# Diode.net
KiCad netlist of a schematic drawn in Altium Designer
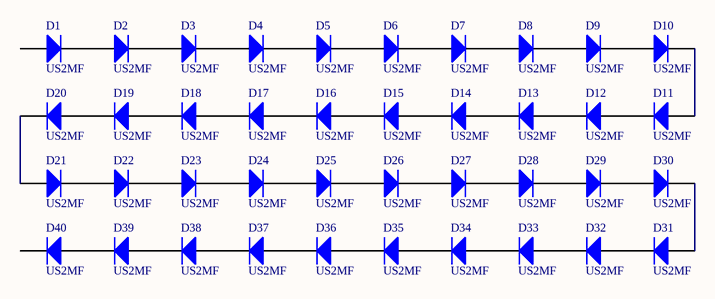
[diagram p0: Diode.SchDoc]

(export (version "E")
  (design (tool "Eeschema 10.0.6"))
  (components
    (comp (ref "D1")
      (value "US2MF")
      (footprint "DO-214AC")
      (description "DIODE - HyperFast 1kV")
      (fields (field (name "LCSC PART #") "C108845"))
      (libsource (lib "JLC_PCB") (part "US2MF"))
    )
    (comp (ref "D2")
      (value "US2MF")
      (footprint "DO-214AC")
      (description "DIODE - HyperFast 1kV")
      (fields (field (name "LCSC PART #") "C108845"))
      (libsource (lib "JLC_PCB") (part "US2MF"))
    )
    (comp (ref "D3")
      (value "US2MF")
      (footprint "DO-214AC")
      (description "DIODE - HyperFast 1kV")
      (fields (field (name "LCSC PART #") "C108845"))
      (libsource (lib "JLC_PCB") (part "US2MF"))
    )
    (comp (ref "D4")
      (value "US2MF")
      (footprint "DO-214AC")
      (description "DIODE - HyperFast 1kV")
      (fields (field (name "LCSC PART #") "C108845"))
      (libsource (lib "JLC_PCB") (part "US2MF"))
    )
    (comp (ref "D5")
      (value "US2MF")
      (footprint "DO-214AC")
      (description "DIODE - HyperFast 1kV")
      (fields (field (name "LCSC PART #") "C108845"))
      (libsource (lib "JLC_PCB") (part "US2MF"))
    )
    (comp (ref "D6")
      (value "US2MF")
      (footprint "DO-214AC")
      (description "DIODE - HyperFast 1kV")
      (fields (field (name "LCSC PART #") "C108845"))
      (libsource (lib "JLC_PCB") (part "US2MF"))
    )
    (comp (ref "D7")
      (value "US2MF")
      (footprint "DO-214AC")
      (description "DIODE - HyperFast 1kV")
      (fields (field (name "LCSC PART #") "C108845"))
      (libsource (lib "JLC_PCB") (part "US2MF"))
    )
    (comp (ref "D8")
      (value "US2MF")
      (footprint "DO-214AC")
      (description "DIODE - HyperFast 1kV")
      (fields (field (name "LCSC PART #") "C108845"))
      (libsource (lib "JLC_PCB") (part "US2MF"))
    )
    (comp (ref "D9")
      (value "US2MF")
      (footprint "DO-214AC")
      (description "DIODE - HyperFast 1kV")
      (fields (field (name "LCSC PART #") "C108845"))
      (libsource (lib "JLC_PCB") (part "US2MF"))
    )
    (comp (ref "D10")
      (value "US2MF")
      (footprint "DO-214AC")
      (description "DIODE - HyperFast 1kV")
      (fields (field (name "LCSC PART #") "C108845"))
      (libsource (lib "JLC_PCB") (part "US2MF"))
    )
    (comp (ref "D11")
      (value "US2MF")
      (footprint "DO-214AC")
      (description "DIODE - HyperFast 1kV")
      (fields (field (name "LCSC PART #") "C108845"))
      (libsource (lib "JLC_PCB") (part "US2MF"))
    )
    (comp (ref "D12")
      (value "US2MF")
      (footprint "DO-214AC")
      (description "DIODE - HyperFast 1kV")
      (fields (field (name "LCSC PART #") "C108845"))
      (libsource (lib "JLC_PCB") (part "US2MF"))
    )
    (comp (ref "D13")
      (value "US2MF")
      (footprint "DO-214AC")
      (description "DIODE - HyperFast 1kV")
      (fields (field (name "LCSC PART #") "C108845"))
      (libsource (lib "JLC_PCB") (part "US2MF"))
    )
    (comp (ref "D14")
      (value "US2MF")
      (footprint "DO-214AC")
      (description "DIODE - HyperFast 1kV")
      (fields (field (name "LCSC PART #") "C108845"))
      (libsource (lib "JLC_PCB") (part "US2MF"))
    )
    (comp (ref "D15")
      (value "US2MF")
      (footprint "DO-214AC")
      (description "DIODE - HyperFast 1kV")
      (fields (field (name "LCSC PART #") "C108845"))
      (libsource (lib "JLC_PCB") (part "US2MF"))
    )
    (comp (ref "D16")
      (value "US2MF")
      (footprint "DO-214AC")
      (description "DIODE - HyperFast 1kV")
      (fields (field (name "LCSC PART #") "C108845"))
      (libsource (lib "JLC_PCB") (part "US2MF"))
    )
    (comp (ref "D17")
      (value "US2MF")
      (footprint "DO-214AC")
      (description "DIODE - HyperFast 1kV")
      (fields (field (name "LCSC PART #") "C108845"))
      (libsource (lib "JLC_PCB") (part "US2MF"))
    )
    (comp (ref "D18")
      (value "US2MF")
      (footprint "DO-214AC")
      (description "DIODE - HyperFast 1kV")
      (fields (field (name "LCSC PART #") "C108845"))
      (libsource (lib "JLC_PCB") (part "US2MF"))
    )
    (comp (ref "D19")
      (value "US2MF")
      (footprint "DO-214AC")
      (description "DIODE - HyperFast 1kV")
      (fields (field (name "LCSC PART #") "C108845"))
      (libsource (lib "JLC_PCB") (part "US2MF"))
    )
    (comp (ref "D20")
      (value "US2MF")
      (footprint "DO-214AC")
      (description "DIODE - HyperFast 1kV")
      (fields (field (name "LCSC PART #") "C108845"))
      (libsource (lib "JLC_PCB") (part "US2MF"))
    )
    (comp (ref "D21")
      (value "US2MF")
      (footprint "DO-214AC")
      (description "DIODE - HyperFast 1kV")
      (fields (field (name "LCSC PART #") "C108845"))
      (libsource (lib "JLC_PCB") (part "US2MF"))
    )
    (comp (ref "D22")
      (value "US2MF")
      (footprint "DO-214AC")
      (description "DIODE - HyperFast 1kV")
      (fields (field (name "LCSC PART #") "C108845"))
      (libsource (lib "JLC_PCB") (part "US2MF"))
    )
    (comp (ref "D23")
      (value "US2MF")
      (footprint "DO-214AC")
      (description "DIODE - HyperFast 1kV")
      (fields (field (name "LCSC PART #") "C108845"))
      (libsource (lib "JLC_PCB") (part "US2MF"))
    )
    (comp (ref "D24")
      (value "US2MF")
      (footprint "DO-214AC")
      (description "DIODE - HyperFast 1kV")
      (fields (field (name "LCSC PART #") "C108845"))
      (libsource (lib "JLC_PCB") (part "US2MF"))
    )
    (comp (ref "D25")
      (value "US2MF")
      (footprint "DO-214AC")
      (description "DIODE - HyperFast 1kV")
      (fields (field (name "LCSC PART #") "C108845"))
      (libsource (lib "JLC_PCB") (part "US2MF"))
    )
    (comp (ref "D26")
      (value "US2MF")
      (footprint "DO-214AC")
      (description "DIODE - HyperFast 1kV")
      (fields (field (name "LCSC PART #") "C108845"))
      (libsource (lib "JLC_PCB") (part "US2MF"))
    )
    (comp (ref "D27")
      (value "US2MF")
      (footprint "DO-214AC")
      (description "DIODE - HyperFast 1kV")
      (fields (field (name "LCSC PART #") "C108845"))
      (libsource (lib "JLC_PCB") (part "US2MF"))
    )
    (comp (ref "D28")
      (value "US2MF")
      (footprint "DO-214AC")
      (description "DIODE - HyperFast 1kV")
      (fields (field (name "LCSC PART #") "C108845"))
      (libsource (lib "JLC_PCB") (part "US2MF"))
    )
    (comp (ref "D29")
      (value "US2MF")
      (footprint "DO-214AC")
      (description "DIODE - HyperFast 1kV")
      (fields (field (name "LCSC PART #") "C108845"))
      (libsource (lib "JLC_PCB") (part "US2MF"))
    )
    (comp (ref "D30")
      (value "US2MF")
      (footprint "DO-214AC")
      (description "DIODE - HyperFast 1kV")
      (fields (field (name "LCSC PART #") "C108845"))
      (libsource (lib "JLC_PCB") (part "US2MF"))
    )
    (comp (ref "D31")
      (value "US2MF")
      (footprint "DO-214AC")
      (description "DIODE - HyperFast 1kV")
      (fields (field (name "LCSC PART #") "C108845"))
      (libsource (lib "JLC_PCB") (part "US2MF"))
    )
    (comp (ref "D32")
      (value "US2MF")
      (footprint "DO-214AC")
      (description "DIODE - HyperFast 1kV")
      (fields (field (name "LCSC PART #") "C108845"))
      (libsource (lib "JLC_PCB") (part "US2MF"))
    )
    (comp (ref "D33")
      (value "US2MF")
      (footprint "DO-214AC")
      (description "DIODE - HyperFast 1kV")
      (fields (field (name "LCSC PART #") "C108845"))
      (libsource (lib "JLC_PCB") (part "US2MF"))
    )
    (comp (ref "D34")
      (value "US2MF")
      (footprint "DO-214AC")
      (description "DIODE - HyperFast 1kV")
      (fields (field (name "LCSC PART #") "C108845"))
      (libsource (lib "JLC_PCB") (part "US2MF"))
    )
    (comp (ref "D35")
      (value "US2MF")
      (footprint "DO-214AC")
      (description "DIODE - HyperFast 1kV")
      (fields (field (name "LCSC PART #") "C108845"))
      (libsource (lib "JLC_PCB") (part "US2MF"))
    )
    (comp (ref "D36")
      (value "US2MF")
      (footprint "DO-214AC")
      (description "DIODE - HyperFast 1kV")
      (fields (field (name "LCSC PART #") "C108845"))
      (libsource (lib "JLC_PCB") (part "US2MF"))
    )
    (comp (ref "D37")
      (value "US2MF")
      (footprint "DO-214AC")
      (description "DIODE - HyperFast 1kV")
      (fields (field (name "LCSC PART #") "C108845"))
      (libsource (lib "JLC_PCB") (part "US2MF"))
    )
    (comp (ref "D38")
      (value "US2MF")
      (footprint "DO-214AC")
      (description "DIODE - HyperFast 1kV")
      (fields (field (name "LCSC PART #") "C108845"))
      (libsource (lib "JLC_PCB") (part "US2MF"))
    )
    (comp (ref "D39")
      (value "US2MF")
      (footprint "DO-214AC")
      (description "DIODE - HyperFast 1kV")
      (fields (field (name "LCSC PART #") "C108845"))
      (libsource (lib "JLC_PCB") (part "US2MF"))
    )
    (comp (ref "D40")
      (value "US2MF")
      (footprint "DO-214AC")
      (description "DIODE - HyperFast 1kV")
      (fields (field (name "LCSC PART #") "C108845"))
      (libsource (lib "JLC_PCB") (part "US2MF"))
    )
  )
  (nets
    (net (code "1") (name "Net-(D1-K)") (class "Default")
      (node (ref "D1") (pin "1") (pinfunction "K_1") (pintype "passive"))
      (node (ref "D2") (pin "2") (pinfunction "A_2") (pintype "passive"))
    )
    (net (code "2") (name "Net-(D2-K)") (class "Default")
      (node (ref "D2") (pin "1") (pinfunction "K_1") (pintype "passive"))
      (node (ref "D3") (pin "2") (pinfunction "A_2") (pintype "passive"))
    )
    (net (code "3") (name "Net-(D3-K)") (class "Default")
      (node (ref "D3") (pin "1") (pinfunction "K_1") (pintype "passive"))
      (node (ref "D4") (pin "2") (pinfunction "A_2") (pintype "passive"))
    )
    (net (code "4") (name "Net-(D4-K)") (class "Default")
      (node (ref "D4") (pin "1") (pinfunction "K_1") (pintype "passive"))
      (node (ref "D5") (pin "2") (pinfunction "A_2") (pintype "passive"))
    )
    (net (code "5") (name "Net-(D5-K)") (class "Default")
      (node (ref "D5") (pin "1") (pinfunction "K_1") (pintype "passive"))
      (node (ref "D6") (pin "2") (pinfunction "A_2") (pintype "passive"))
    )
    (net (code "6") (name "Net-(D6-K)") (class "Default")
      (node (ref "D6") (pin "1") (pinfunction "K_1") (pintype "passive"))
      (node (ref "D7") (pin "2") (pinfunction "A_2") (pintype "passive"))
    )
    (net (code "7") (name "Net-(D7-K)") (class "Default")
      (node (ref "D7") (pin "1") (pinfunction "K_1") (pintype "passive"))
      (node (ref "D8") (pin "2") (pinfunction "A_2") (pintype "passive"))
    )
    (net (code "8") (name "Net-(D8-K)") (class "Default")
      (node (ref "D8") (pin "1") (pinfunction "K_1") (pintype "passive"))
      (node (ref "D9") (pin "2") (pinfunction "A_2") (pintype "passive"))
    )
    (net (code "9") (name "Net-(D10-A)") (class "Default")
      (node (ref "D10") (pin "2") (pinfunction "A_2") (pintype "passive"))
      (node (ref "D9") (pin "1") (pinfunction "K_1") (pintype "passive"))
    )
    (net (code "10") (name "Net-(D10-K)") (class "Default")
      (node (ref "D10") (pin "1") (pinfunction "K_1") (pintype "passive"))
      (node (ref "D11") (pin "2") (pinfunction "A_2") (pintype "passive"))
    )
    (net (code "11") (name "Net-(D11-K)") (class "Default")
      (node (ref "D11") (pin "1") (pinfunction "K_1") (pintype "passive"))
      (node (ref "D12") (pin "2") (pinfunction "A_2") (pintype "passive"))
    )
    (net (code "12") (name "Net-(D12-K)") (class "Default")
      (node (ref "D12") (pin "1") (pinfunction "K_1") (pintype "passive"))
      (node (ref "D13") (pin "2") (pinfunction "A_2") (pintype "passive"))
    )
    (net (code "13") (name "Net-(D13-K)") (class "Default")
      (node (ref "D13") (pin "1") (pinfunction "K_1") (pintype "passive"))
      (node (ref "D14") (pin "2") (pinfunction "A_2") (pintype "passive"))
    )
    (net (code "14") (name "Net-(D14-K)") (class "Default")
      (node (ref "D14") (pin "1") (pinfunction "K_1") (pintype "passive"))
      (node (ref "D15") (pin "2") (pinfunction "A_2") (pintype "passive"))
    )
    (net (code "15") (name "Net-(D15-K)") (class "Default")
      (node (ref "D15") (pin "1") (pinfunction "K_1") (pintype "passive"))
      (node (ref "D16") (pin "2") (pinfunction "A_2") (pintype "passive"))
    )
    (net (code "16") (name "Net-(D16-K)") (class "Default")
      (node (ref "D16") (pin "1") (pinfunction "K_1") (pintype "passive"))
      (node (ref "D17") (pin "2") (pinfunction "A_2") (pintype "passive"))
    )
    (net (code "17") (name "Net-(D17-K)") (class "Default")
      (node (ref "D17") (pin "1") (pinfunction "K_1") (pintype "passive"))
      (node (ref "D18") (pin "2") (pinfunction "A_2") (pintype "passive"))
    )
    (net (code "18") (name "Net-(D18-K)") (class "Default")
      (node (ref "D18") (pin "1") (pinfunction "K_1") (pintype "passive"))
      (node (ref "D19") (pin "2") (pinfunction "A_2") (pintype "passive"))
    )
    (net (code "19") (name "Net-(D19-K)") (class "Default")
      (node (ref "D19") (pin "1") (pinfunction "K_1") (pintype "passive"))
      (node (ref "D20") (pin "2") (pinfunction "A_2") (pintype "passive"))
    )
    (net (code "20") (name "Net-(D20-K)") (class "Default")
      (node (ref "D20") (pin "1") (pinfunction "K_1") (pintype "passive"))
      (node (ref "D21") (pin "2") (pinfunction "A_2") (pintype "passive"))
    )
    (net (code "21") (name "Net-(D21-K)") (class "Default")
      (node (ref "D21") (pin "1") (pinfunction "K_1") (pintype "passive"))
      (node (ref "D22") (pin "2") (pinfunction "A_2") (pintype "passive"))
    )
    (net (code "22") (name "Net-(D22-K)") (class "Default")
      (node (ref "D22") (pin "1") (pinfunction "K_1") (pintype "passive"))
      (node (ref "D23") (pin "2") (pinfunction "A_2") (pintype "passive"))
    )
    (net (code "23") (name "Net-(D23-K)") (class "Default")
      (node (ref "D23") (pin "1") (pinfunction "K_1") (pintype "passive"))
      (node (ref "D24") (pin "2") (pinfunction "A_2") (pintype "passive"))
    )
    (net (code "24") (name "Net-(D24-K)") (class "Default")
      (node (ref "D24") (pin "1") (pinfunction "K_1") (pintype "passive"))
      (node (ref "D25") (pin "2") (pinfunction "A_2") (pintype "passive"))
    )
    (net (code "25") (name "Net-(D25-K)") (class "Default")
      (node (ref "D25") (pin "1") (pinfunction "K_1") (pintype "passive"))
      (node (ref "D26") (pin "2") (pinfunction "A_2") (pintype "passive"))
    )
    (net (code "26") (name "Net-(D26-K)") (class "Default")
      (node (ref "D26") (pin "1") (pinfunction "K_1") (pintype "passive"))
      (node (ref "D27") (pin "2") (pinfunction "A_2") (pintype "passive"))
    )
    (net (code "27") (name "Net-(D27-K)") (class "Default")
      (node (ref "D27") (pin "1") (pinfunction "K_1") (pintype "passive"))
      (node (ref "D28") (pin "2") (pinfunction "A_2") (pintype "passive"))
    )
    (net (code "28") (name "Net-(D28-K)") (class "Default")
      (node (ref "D28") (pin "1") (pinfunction "K_1") (pintype "passive"))
      (node (ref "D29") (pin "2") (pinfunction "A_2") (pintype "passive"))
    )
    (net (code "29") (name "Net-(D29-K)") (class "Default")
      (node (ref "D29") (pin "1") (pinfunction "K_1") (pintype "passive"))
      (node (ref "D30") (pin "2") (pinfunction "A_2") (pintype "passive"))
    )
    (net (code "30") (name "Net-(D30-K)") (class "Default")
      (node (ref "D30") (pin "1") (pinfunction "K_1") (pintype "passive"))
      (node (ref "D31") (pin "2") (pinfunction "A_2") (pintype "passive"))
    )
    (net (code "31") (name "Net-(D31-K)") (class "Default")
      (node (ref "D31") (pin "1") (pinfunction "K_1") (pintype "passive"))
      (node (ref "D32") (pin "2") (pinfunction "A_2") (pintype "passive"))
    )
    (net (code "32") (name "Net-(D32-K)") (class "Default")
      (node (ref "D32") (pin "1") (pinfunction "K_1") (pintype "passive"))
      (node (ref "D33") (pin "2") (pinfunction "A_2") (pintype "passive"))
    )
    (net (code "33") (name "Net-(D33-K)") (class "Default")
      (node (ref "D33") (pin "1") (pinfunction "K_1") (pintype "passive"))
      (node (ref "D34") (pin "2") (pinfunction "A_2") (pintype "passive"))
    )
    (net (code "34") (name "Net-(D34-K)") (class "Default")
      (node (ref "D34") (pin "1") (pinfunction "K_1") (pintype "passive"))
      (node (ref "D35") (pin "2") (pinfunction "A_2") (pintype "passive"))
    )
    (net (code "35") (name "Net-(D35-K)") (class "Default")
      (node (ref "D35") (pin "1") (pinfunction "K_1") (pintype "passive"))
      (node (ref "D36") (pin "2") (pinfunction "A_2") (pintype "passive"))
    )
    (net (code "36") (name "Net-(D36-K)") (class "Default")
      (node (ref "D36") (pin "1") (pinfunction "K_1") (pintype "passive"))
      (node (ref "D37") (pin "2") (pinfunction "A_2") (pintype "passive"))
    )
    (net (code "37") (name "Net-(D37-K)") (class "Default")
      (node (ref "D37") (pin "1") (pinfunction "K_1") (pintype "passive"))
      (node (ref "D38") (pin "2") (pinfunction "A_2") (pintype "passive"))
    )
    (net (code "38") (name "Net-(D38-K)") (class "Default")
      (node (ref "D38") (pin "1") (pinfunction "K_1") (pintype "passive"))
      (node (ref "D39") (pin "2") (pinfunction "A_2") (pintype "passive"))
    )
    (net (code "39") (name "Net-(D39-K)") (class "Default")
      (node (ref "D39") (pin "1") (pinfunction "K_1") (pintype "passive"))
      (node (ref "D40") (pin "2") (pinfunction "A_2") (pintype "passive"))
    )
    (net (code "40") (name "unconnected-(D1-A-Pad2)") (class "Default")
      (node (ref "D1") (pin "2") (pinfunction "A_2") (pintype "passive"))
    )
    (net (code "41") (name "unconnected-(D40-K-Pad1)") (class "Default")
      (node (ref "D40") (pin "1") (pinfunction "K_1") (pintype "passive"))
    )
  )
)
